# Sheet1.net
KiCad netlist of a schematic drawn in Altium Designer
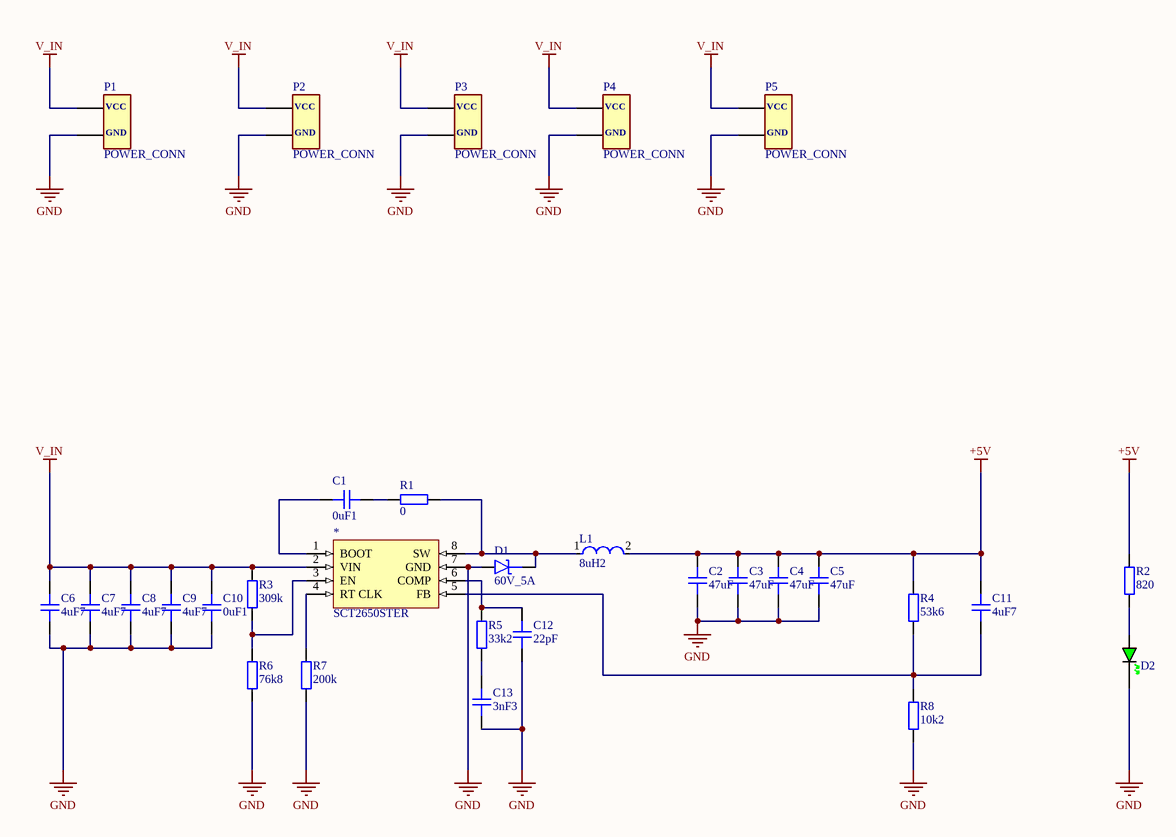
[diagram p0: Sheet1.SchDoc]

(export (version "E")
  (design (tool "Eeschema 10.0.6"))
  (components
    (comp (ref "*")
      (value "SCT2650STER")
      (footprint "SCT2650STER")
      (libsource (lib "Schlib1") (part "SCT2650STER"))
    )
    (comp (ref "C1")
      (value "0uF1")
      (footprint "CAP_0805")
      (description "Capacitor SMD 0805")
      (libsource (lib "Schematic-Lib-PhilsLab") (part "CAP_0805"))
    )
    (comp (ref "C2")
      (value "47uF")
      (footprint "CAP_0805")
      (description "Capacitor SMD 0805")
      (libsource (lib "Schematic-Lib-PhilsLab") (part "CAP_0805"))
    )
    (comp (ref "C3")
      (value "47uF")
      (footprint "CAP_0805")
      (description "Capacitor SMD 0805")
      (libsource (lib "Schematic-Lib-PhilsLab") (part "CAP_0805"))
    )
    (comp (ref "C4")
      (value "47uF")
      (footprint "CAP_0805")
      (description "Capacitor SMD 0805")
      (libsource (lib "Schematic-Lib-PhilsLab") (part "CAP_0805"))
    )
    (comp (ref "C5")
      (value "47uF")
      (footprint "CAP_0805")
      (description "Capacitor SMD 0805")
      (libsource (lib "Schematic-Lib-PhilsLab") (part "CAP_0805"))
    )
    (comp (ref "C6")
      (value "4uF7")
      (footprint "CAP_0805")
      (description "Capacitor SMD 0805")
      (libsource (lib "Schematic-Lib-PhilsLab") (part "CAP_0805"))
    )
    (comp (ref "C7")
      (value "4uF7")
      (footprint "CAP_0805")
      (description "Capacitor SMD 0805")
      (libsource (lib "Schematic-Lib-PhilsLab") (part "CAP_0805"))
    )
    (comp (ref "C8")
      (value "4uF7")
      (footprint "CAP_0805")
      (description "Capacitor SMD 0805")
      (libsource (lib "Schematic-Lib-PhilsLab") (part "CAP_0805"))
    )
    (comp (ref "C9")
      (value "4uF7")
      (footprint "CAP_0805")
      (description "Capacitor SMD 0805")
      (libsource (lib "Schematic-Lib-PhilsLab") (part "CAP_0805"))
    )
    (comp (ref "C10")
      (value "0uF1")
      (footprint "CAP_0805")
      (description "Capacitor SMD 0805")
      (libsource (lib "Schematic-Lib-PhilsLab") (part "CAP_0805"))
    )
    (comp (ref "C11")
      (value "4uF7")
      (footprint "CAP_0805")
      (description "Capacitor SMD 0805")
      (libsource (lib "Schematic-Lib-PhilsLab") (part "CAP_0805"))
    )
    (comp (ref "C12")
      (value "22pF")
      (footprint "CAP_0805")
      (description "Capacitor SMD 0805")
      (libsource (lib "Schematic-Lib-PhilsLab") (part "CAP_0805"))
    )
    (comp (ref "C13")
      (value "3nF3")
      (footprint "CAP_0805")
      (description "Capacitor SMD 0805")
      (libsource (lib "Schematic-Lib-PhilsLab") (part "CAP_0805"))
    )
    (comp (ref "D1")
      (value "60V_5A")
      (footprint "DO-214AC-2 (SMA)")
      (description "Diode Schottky SMD SMA (DO-214AA)")
      (libsource (lib "Schematic-Lib-PhilsLab") (part "D_SCHOTTKY_SMA"))
    )
    (comp (ref "D2")
      (value "GREEN")
      (footprint "LED_0805_GREEN")
      (description "LED 0805 GREEN SMD")
      (libsource (lib "Schematic-Lib-PhilsLab") (part "LED_0805_GREEN"))
    )
    (comp (ref "L1")
      (value "8uH2")
      (footprint "FP-CDRH104R-MFG")
      (description "FIXED IND 5.2UH 6A 22 MOHM SMD")
      (fields (field (name "TOLERANCE") "30%"))
      (libsource (lib "Altium Content Vault") (part "725321dda6339637d4d059423bc1c3c"))
    )
    (comp (ref "P1")
      (value "POWER_CONN")
      (footprint "POWER_CONN")
      (description "Li-on Battery Power Connector")
      (libsource (lib "Flight_Controller_Board_Design") (part "POWER_CONN"))
    )
    (comp (ref "P2")
      (value "POWER_CONN")
      (footprint "POWER_CONN")
      (description "Li-on Battery Power Connector")
      (libsource (lib "Flight_Controller_Board_Design") (part "POWER_CONN"))
    )
    (comp (ref "P3")
      (value "POWER_CONN")
      (footprint "POWER_CONN")
      (description "Li-on Battery Power Connector")
      (libsource (lib "Flight_Controller_Board_Design") (part "POWER_CONN"))
    )
    (comp (ref "P4")
      (value "POWER_CONN")
      (footprint "POWER_CONN")
      (description "Li-on Battery Power Connector")
      (libsource (lib "Flight_Controller_Board_Design") (part "POWER_CONN"))
    )
    (comp (ref "P5")
      (value "POWER_CONN")
      (footprint "POWER_CONN")
      (description "Li-on Battery Power Connector")
      (libsource (lib "Flight_Controller_Board_Design") (part "POWER_CONN"))
    )
    (comp (ref "R1")
      (value "0")
      (footprint "RES_0805")
      (description "Resistor SMD 0805")
      (libsource (lib "Schematic-Lib-PhilsLab") (part "RES_0805"))
    )
    (comp (ref "R2")
      (value "820")
      (footprint "RES_0805")
      (description "Resistor SMD 0805")
      (libsource (lib "Schematic-Lib-PhilsLab") (part "RES_0805"))
    )
    (comp (ref "R3")
      (value "309k")
      (footprint "RES_0805")
      (description "Resistor SMD 0805")
      (libsource (lib "Schematic-Lib-PhilsLab") (part "RES_0805"))
    )
    (comp (ref "R4")
      (value "53k6")
      (footprint "RES_0805")
      (description "Resistor SMD 0805")
      (libsource (lib "Schematic-Lib-PhilsLab") (part "RES_0805"))
    )
    (comp (ref "R5")
      (value "33k2")
      (footprint "RES_0805")
      (description "Resistor SMD 0805")
      (libsource (lib "Schematic-Lib-PhilsLab") (part "RES_0805"))
    )
    (comp (ref "R6")
      (value "76k8")
      (footprint "RES_0805")
      (description "Resistor SMD 0805")
      (libsource (lib "Schematic-Lib-PhilsLab") (part "RES_0805"))
    )
    (comp (ref "R7")
      (value "200k")
      (footprint "RES_0805")
      (description "Resistor SMD 0805")
      (libsource (lib "Schematic-Lib-PhilsLab") (part "RES_0805"))
    )
    (comp (ref "R8")
      (value "10k2")
      (footprint "RES_0805")
      (description "Resistor SMD 0805")
      (libsource (lib "Schematic-Lib-PhilsLab") (part "RES_0805"))
    )
  )
  (nets
    (net (code "1") (name "+5V") (class "Default")
      (node (ref "C11") (pin "1") (pinfunction "1_1") (pintype "passive"))
      (node (ref "C2") (pin "2") (pinfunction "2_2") (pintype "passive"))
      (node (ref "C3") (pin "2") (pinfunction "2_2") (pintype "passive"))
      (node (ref "C4") (pin "2") (pinfunction "2_2") (pintype "passive"))
      (node (ref "C5") (pin "2") (pinfunction "2_2") (pintype "passive"))
      (node (ref "L1") (pin "2") (pinfunction "2_2") (pintype "passive"))
      (node (ref "R2") (pin "2") (pinfunction "2_2") (pintype "passive"))
      (node (ref "R4") (pin "2") (pinfunction "2_2") (pintype "passive"))
    )
    (net (code "2") (name "GND") (class "Default")
      (node (ref "*") (pin "7") (pinfunction "GND_7") (pintype "input"))
      (node (ref "C10") (pin "1") (pinfunction "1_1") (pintype "passive"))
      (node (ref "C12") (pin "2") (pinfunction "2_2") (pintype "passive"))
      (node (ref "C13") (pin "2") (pinfunction "2_2") (pintype "passive"))
      (node (ref "C2") (pin "1") (pinfunction "1_1") (pintype "passive"))
      (node (ref "C3") (pin "1") (pinfunction "1_1") (pintype "passive"))
      (node (ref "C4") (pin "1") (pinfunction "1_1") (pintype "passive"))
      (node (ref "C5") (pin "1") (pinfunction "1_1") (pintype "passive"))
      (node (ref "C6") (pin "1") (pinfunction "1_1") (pintype "passive"))
      (node (ref "C7") (pin "1") (pinfunction "1_1") (pintype "passive"))
      (node (ref "C8") (pin "1") (pinfunction "1_1") (pintype "passive"))
      (node (ref "C9") (pin "1") (pinfunction "1_1") (pintype "passive"))
      (node (ref "D1") (pin "A") (pinfunction "A_A") (pintype "passive"))
      (node (ref "D2") (pin "K") (pinfunction "K_K") (pintype "passive"))
      (node (ref "P1") (pin "1") (pinfunction "GND_1") (pintype "passive"))
      (node (ref "P2") (pin "1") (pinfunction "GND_1") (pintype "passive"))
      (node (ref "P3") (pin "1") (pinfunction "GND_1") (pintype "passive"))
      (node (ref "P4") (pin "1") (pinfunction "GND_1") (pintype "passive"))
      (node (ref "P5") (pin "1") (pinfunction "GND_1") (pintype "passive"))
      (node (ref "R6") (pin "1") (pinfunction "1_1") (pintype "passive"))
      (node (ref "R7") (pin "1") (pinfunction "1_1") (pintype "passive"))
      (node (ref "R8") (pin "1") (pinfunction "1_1") (pintype "passive"))
    )
    (net (code "3") (name "Net-(*-BOOT)") (class "Default")
      (node (ref "*") (pin "1") (pinfunction "BOOT_1") (pintype "input"))
      (node (ref "C1") (pin "2") (pinfunction "2_2") (pintype "passive"))
    )
    (net (code "4") (name "Net-(*-COMP)") (class "Default")
      (node (ref "*") (pin "6") (pinfunction "COMP_6") (pintype "input"))
      (node (ref "C12") (pin "1") (pinfunction "1_1") (pintype "passive"))
      (node (ref "R5") (pin "2") (pinfunction "2_2") (pintype "passive"))
    )
    (net (code "5") (name "Net-(*-EN)") (class "Default")
      (node (ref "*") (pin "3") (pinfunction "EN_3") (pintype "input"))
      (node (ref "R3") (pin "1") (pinfunction "1_1") (pintype "passive"))
      (node (ref "R6") (pin "2") (pinfunction "2_2") (pintype "passive"))
    )
    (net (code "6") (name "Net-(*-FB)") (class "Default")
      (node (ref "*") (pin "5") (pinfunction "FB_5") (pintype "input"))
      (node (ref "C11") (pin "2") (pinfunction "2_2") (pintype "passive"))
      (node (ref "R4") (pin "1") (pinfunction "1_1") (pintype "passive"))
      (node (ref "R8") (pin "2") (pinfunction "2_2") (pintype "passive"))
    )
    (net (code "7") (name "Net-(*-RT_CLK)") (class "Default")
      (node (ref "*") (pin "4") (pinfunction "RT_CLK_4") (pintype "input"))
      (node (ref "R7") (pin "2") (pinfunction "2_2") (pintype "passive"))
    )
    (net (code "8") (name "Net-(*-SW)") (class "Default")
      (node (ref "*") (pin "8") (pinfunction "SW_8") (pintype "input"))
      (node (ref "D1") (pin "K") (pinfunction "K_K") (pintype "passive"))
      (node (ref "L1") (pin "1") (pinfunction "1_1") (pintype "passive"))
      (node (ref "R1") (pin "1") (pinfunction "1_1") (pintype "passive"))
    )
    (net (code "9") (name "Net-(C1-Pad1)") (class "Default")
      (node (ref "C1") (pin "1") (pinfunction "1_1") (pintype "passive"))
      (node (ref "R1") (pin "2") (pinfunction "2_2") (pintype "passive"))
    )
    (net (code "10") (name "Net-(C13-Pad1)") (class "Default")
      (node (ref "C13") (pin "1") (pinfunction "1_1") (pintype "passive"))
      (node (ref "R5") (pin "1") (pinfunction "1_1") (pintype "passive"))
    )
    (net (code "11") (name "Net-(D2-PadA)") (class "Default")
      (node (ref "D2") (pin "A") (pinfunction "A_A") (pintype "passive"))
      (node (ref "R2") (pin "1") (pinfunction "1_1") (pintype "passive"))
    )
    (net (code "12") (name "V_IN") (class "Default")
      (node (ref "*") (pin "2") (pinfunction "VIN_2") (pintype "input"))
      (node (ref "C10") (pin "2") (pinfunction "2_2") (pintype "passive"))
      (node (ref "C6") (pin "2") (pinfunction "2_2") (pintype "passive"))
      (node (ref "C7") (pin "2") (pinfunction "2_2") (pintype "passive"))
      (node (ref "C8") (pin "2") (pinfunction "2_2") (pintype "passive"))
      (node (ref "C9") (pin "2") (pinfunction "2_2") (pintype "passive"))
      (node (ref "P1") (pin "0") (pinfunction "VCC_0") (pintype "passive"))
      (node (ref "P2") (pin "0") (pinfunction "VCC_0") (pintype "passive"))
      (node (ref "P3") (pin "0") (pinfunction "VCC_0") (pintype "passive"))
      (node (ref "P4") (pin "0") (pinfunction "VCC_0") (pintype "passive"))
      (node (ref "P5") (pin "0") (pinfunction "VCC_0") (pintype "passive"))
      (node (ref "R3") (pin "2") (pinfunction "2_2") (pintype "passive"))
    )
  )
)
